# LoRaWAN_CO2_measurement_Device.net
KiCad netlist of a schematic drawn in Altium Designer
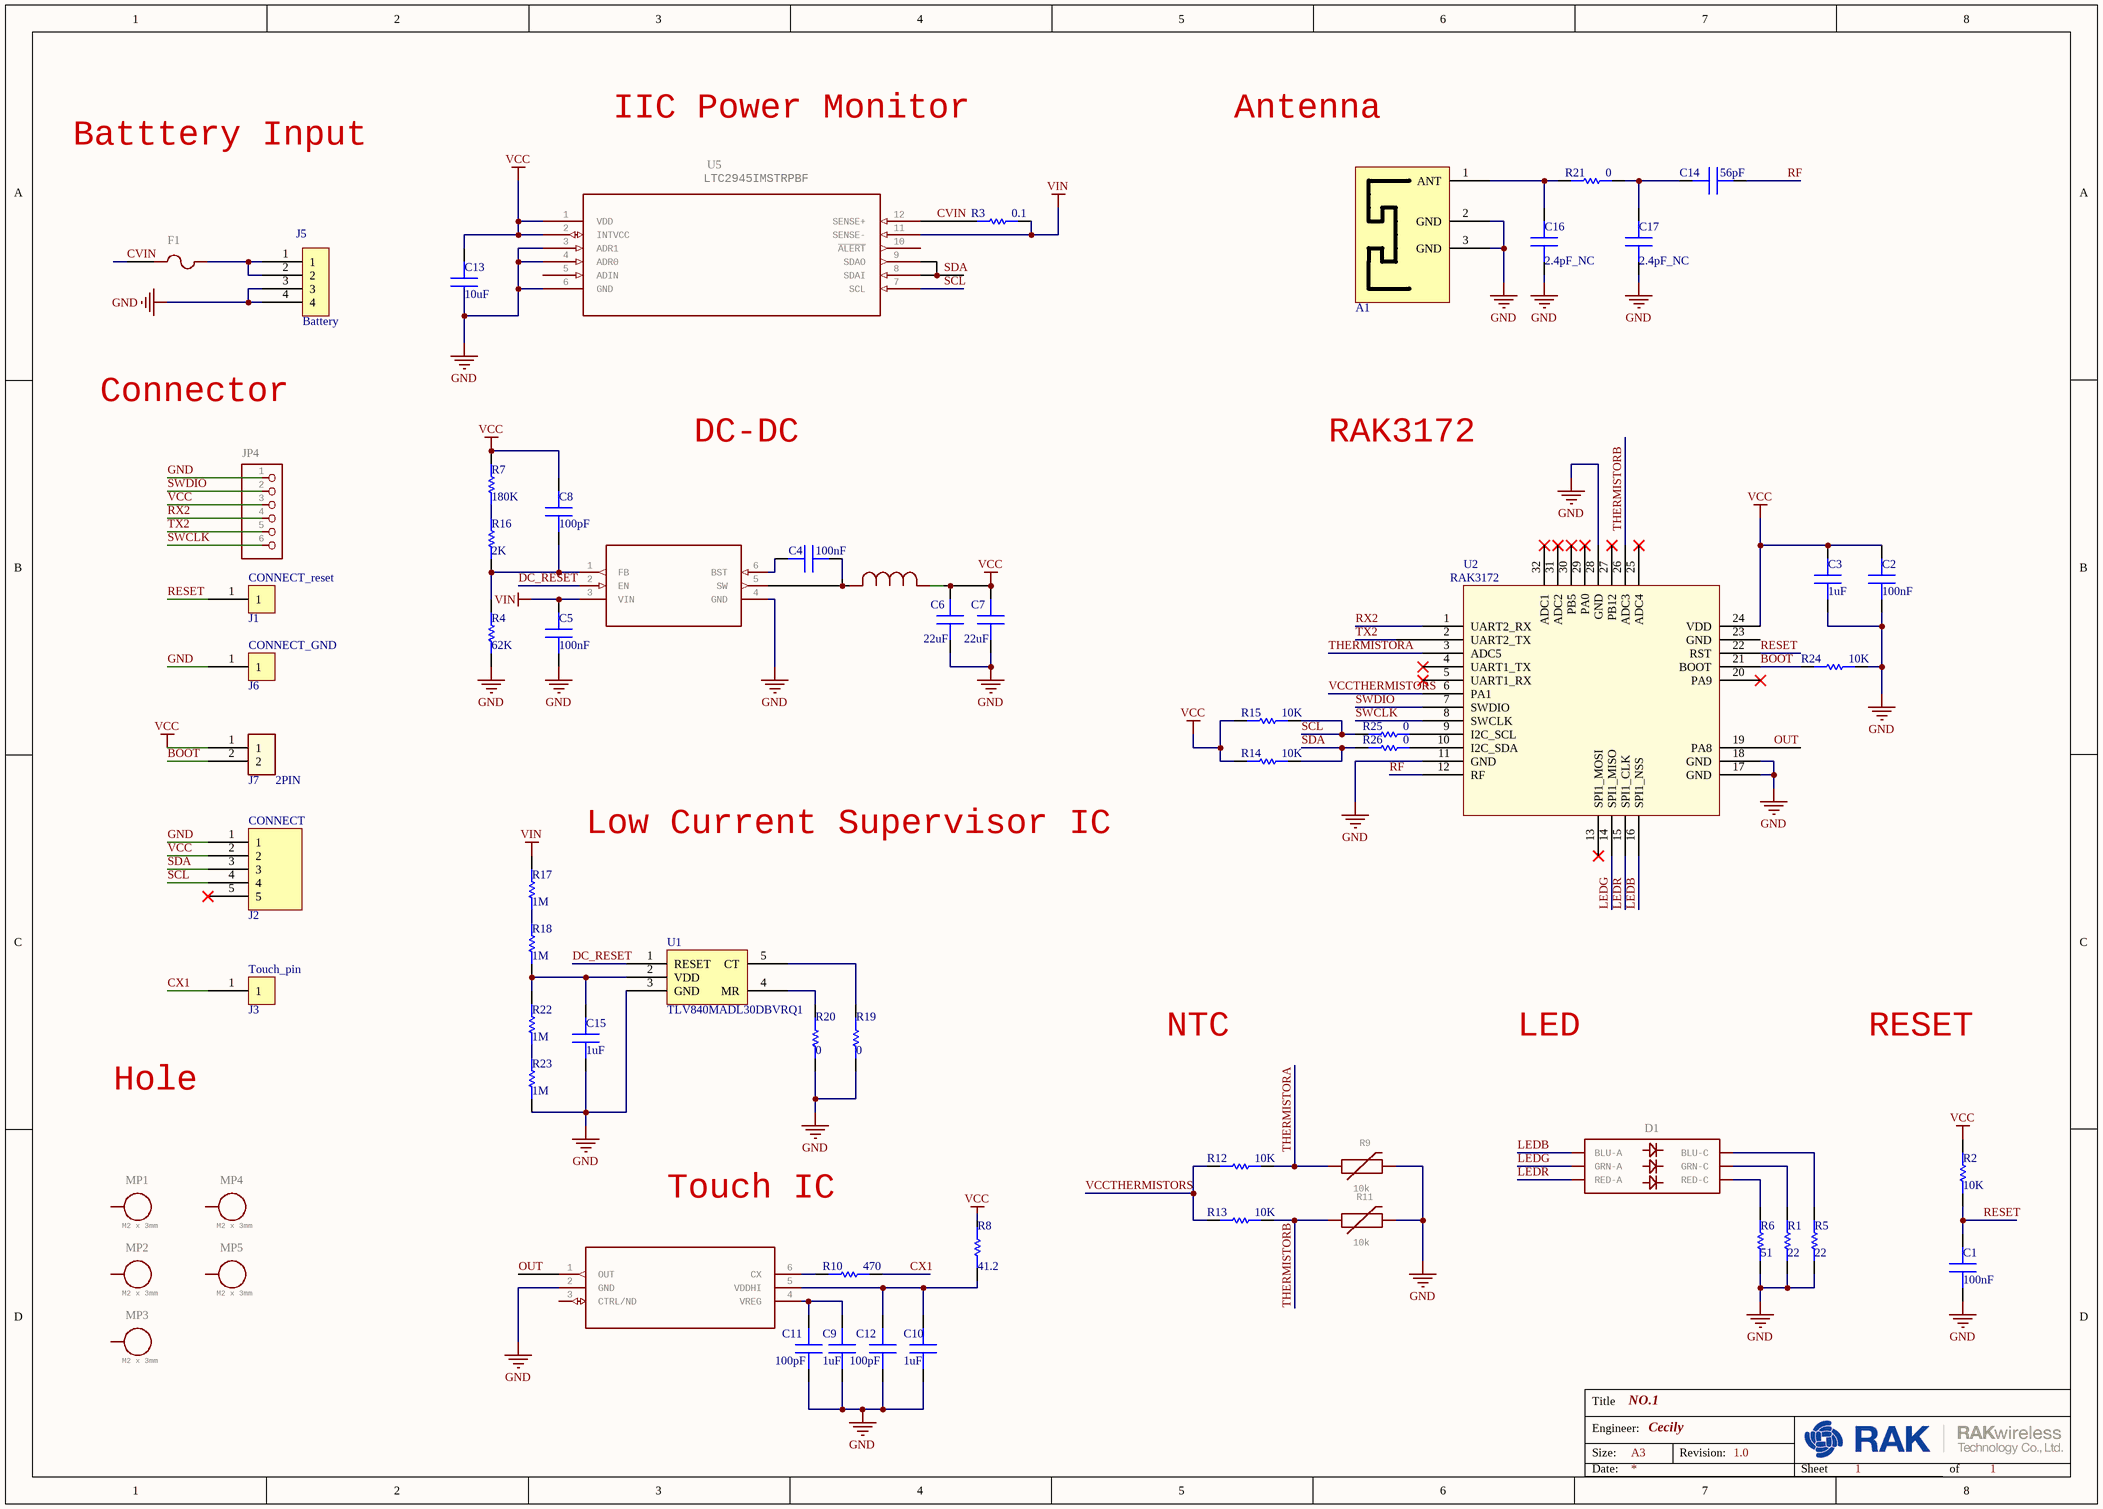
[diagram p0: LoRaWAN CO2 measurement Device.SchDoc]

(export (version "E")
  (design (tool "Eeschema 10.0.6"))
  (components
    (comp (ref "A1")
      (value "ANT_LORA_Alarm_Button")
      (footprint "ANT_LORA_Alarm_Button")
      (libsource (lib "LIBRARY_ZWW_Library") (part "ANT_LORA_Alarm_Button"))
    )
    (comp (ref "C1")
      (value "100nF")
      (footprint "sc0402")
      (description "Capacitor-10V-100nF-±10%-X5R -0402")
      (fields (field (name "MANUFACTURER") "YAGEO") (field (name "TOLERANCE") "±10%"))
      (libsource (lib "RAK_Database_Lib_2022") (part "CAPACITOR NP"))
    )
    (comp (ref "C2")
      (value "100nF")
      (footprint "sc0402")
      (description "Capacitor-10V-100nF-±10%-X5R -0402")
      (fields (field (name "MANUFACTURER") "YAGEO") (field (name "TOLERANCE") "±10%"))
      (libsource (lib "RAK_Database_Lib_2022") (part "CAPACITOR NP"))
    )
    (comp (ref "C3")
      (value "1uF")
      (footprint "sc0402")
      (description "Capacitor-10V-1uF-±10%-X5R-0402")
      (fields (field (name "MANUFACTURER") "YAGEO") (field (name "TOLERANCE") "±10%"))
      (libsource (lib "RAK_Database_Lib_2022") (part "CAPACITOR NP"))
    )
    (comp (ref "C4")
      (value "100nF")
      (footprint "sc0402")
      (description "Capacitor-10V-100nF-±10%-X5R -0402")
      (fields (field (name "MANUFACTURER") "YAGEO") (field (name "TOLERANCE") "±10%"))
      (libsource (lib "RAK_Database_Lib_2022") (part "CAPACITOR NP"))
    )
    (comp (ref "C5")
      (value "100nF")
      (footprint "sc0402")
      (description "Capacitor-10V-100nF-±10%-X5R -0402")
      (fields (field (name "MANUFACTURER") "YAGEO") (field (name "TOLERANCE") "±10%"))
      (libsource (lib "RAK_Database_Lib_2022") (part "CAPACITOR NP"))
    )
    (comp (ref "C6")
      (value "22uF")
      (footprint "sc0805")
      (description "Capacitor-25V-22uF-±20%-X5R-0805")
      (fields (field (name "MANUFACTURER") "MURATA") (field (name "TOLERANCE") "±20%"))
      (libsource (lib "RAK_Database_Lib_2022") (part "CAPACITOR NP"))
    )
    (comp (ref "C7")
      (value "22uF")
      (footprint "sc0805")
      (description "Capacitor-25V-22uF-±20%-X5R-0805")
      (fields (field (name "MANUFACTURER") "MURATA") (field (name "TOLERANCE") "±20%"))
      (libsource (lib "RAK_Database_Lib_2022") (part "CAPACITOR NP"))
    )
    (comp (ref "C8")
      (value "100pF")
      (footprint "sc0402")
      (description "Capacitor-50V-100pF-±5%-NPO-0402")
      (fields (field (name "MANUFACTURER") "YAGEO") (field (name "TOLERANCE") "±5%"))
      (libsource (lib "RAK_Database_Lib_2022") (part "CAPACITOR NP"))
    )
    (comp (ref "C9")
      (value "1uF")
      (footprint "sc0402")
      (description "Capacitor-10V-1uF-±10%-X5R-0402")
      (fields (field (name "MANUFACTURER") "YAGEO") (field (name "TOLERANCE") "±10%"))
      (libsource (lib "RAK_Database_Lib_2022") (part "CAPACITOR NP"))
    )
    (comp (ref "C10")
      (value "1uF")
      (footprint "sc0402")
      (description "Capacitor-10V-1uF-±10%-X5R-0402")
      (fields (field (name "MANUFACTURER") "YAGEO") (field (name "TOLERANCE") "±10%"))
      (libsource (lib "RAK_Database_Lib_2022") (part "CAPACITOR NP"))
    )
    (comp (ref "C11")
      (value "100pF")
      (footprint "sc0402")
      (description "Capacitor-50V-100pF-±5%-NPO-0402")
      (fields (field (name "MANUFACTURER") "YAGEO") (field (name "TOLERANCE") "±5%"))
      (libsource (lib "RAK_Database_Lib_2022") (part "CAPACITOR NP"))
    )
    (comp (ref "C12")
      (value "100pF")
      (footprint "sc0402")
      (description "Capacitor-50V-100pF-±5%-NPO-0402")
      (fields (field (name "MANUFACTURER") "YAGEO") (field (name "TOLERANCE") "±5%"))
      (libsource (lib "RAK_Database_Lib_2022") (part "CAPACITOR NP"))
    )
    (comp (ref "C13")
      (value "10uF")
      (footprint "sc0402")
      (description "Capacitor-10V-10uF-±20%-X5R-0402")
      (fields (field (name "MANUFACTURER") "YAGEO") (field (name "TOLERANCE") "±20%"))
      (libsource (lib "RAK_Database_Lib_2022") (part "CAPACITOR NP"))
    )
    (comp (ref "C14")
      (value "56pF")
      (footprint "sc0402")
      (description "Capacitor-50V-56pF-±5%-COG-0402")
      (fields (field (name "MANUFACTURER") "Murata") (field (name "TOLERANCE") "±5%"))
      (libsource (lib "RAK_Database_Lib_2022") (part "CAPACITOR NP"))
    )
    (comp (ref "C15")
      (value "1uF")
      (footprint "sc0402")
      (description "Capacitor-10V-1uF-±10%-X5R-0402")
      (fields (field (name "MANUFACTURER") "YAGEO") (field (name "TOLERANCE") "±10%"))
      (libsource (lib "RAK_Database_Lib_2022") (part "CAPACITOR NP"))
    )
    (comp (ref "C16")
      (value "2.4pF_NC")
      (footprint "sc0402")
      (description "Capacitor-50V-2.4pF-±0.1pF-COG-0402")
      (fields (field (name "MANUFACTURER") "MuRATA") (field (name "TOLERANCE") "±0.1pF"))
      (libsource (lib "RAK_Database_Lib_2022") (part "CAPACITOR NP"))
    )
    (comp (ref "C17")
      (value "2.4pF_NC")
      (footprint "sc0402")
      (description "Capacitor-50V-2.4pF-±0.1pF-COG-0402")
      (fields (field (name "MANUFACTURER") "MuRATA") (field (name "TOLERANCE") "±0.1pF"))
      (libsource (lib "RAK_Database_Lib_2022") (part "CAPACITOR NP"))
    )
    (comp (ref "CONNECT")
      (value "J2")
      (footprint "circle1*5_0.7_1.106")
      (libsource (lib "CONNECT") (part "CONNECT"))
    )
    (comp (ref "CONNECT_GND")
      (value "J6")
      (footprint "circle1*1_1.016_1.788")
      (libsource (lib "CONNECT_1") (part "CONNECT_1"))
    )
    (comp (ref "CONNECT_reset")
      (value "J1")
      (footprint "circle1*1_1.016_1.788")
      (libsource (lib "CONNECT_1") (part "CONNECT_1"))
    )
    (comp (ref "D1")
      (value "LED-RGBBRG")
      (footprint "LED-TRICOLOR-5050")
      (libsource (lib "SparkFun-LED") (part "LED-RGBBRG"))
    )
    (comp (ref "F1")
      (value "0031.7701.11")
      (footprint "FUSE_0031.7701.11_SCH")
      (fields
        (field (name "LIBRARYNAME") "fusible")
        (field (name "COPYRIGHT") "Copyright (C) 2024 Ultra Librarian. All rights reserved.")
      )
      (libsource (lib "fusible") (part "0031.7701.11"))
    )
    (comp (ref "J5") (value "Battery") (footprint "Battery_Con") (libsource (lib "Cecily") (part "Battery")))
    (comp (ref "J7")
      (value "2PIN")
      (footprint "SIP-2P")
      (description "Conn Header-Male Pin-1*2Pos-Straight-PH2.54-Through Hole-Pole3.0mm-Mating6mm-Body2.54mm")
      (fields (field (name "MANUFACTURER") "STZ01") (field (name "PART NUMBER") "ST-PH-254-0087"))
      (libsource (lib "RAK_Database_Lib_2022") (part "CONN-2"))
    )
    (comp (ref "JP4")
      (value "PINHD-1X6CB")
      (footprint "1X06-CLEANBIG")
      (description "PIN HEADER")
      (fields (field (name "LIBRARYNAME") "holes_no_keep"))
      (libsource (lib "holes_no_keep") (part "PINHD-1X6CB"))
    )
    (comp (ref "L1")
      (value "SD14-6R9-R")
      (footprint "IND_CB_SD14")
      (fields
        (field (name "LIBRARYNAME") "inductor_eaton_6.9uh")
        (field (name "COPYRIGHT") "Copyright (C) 2024 Ultra Librarian. All rights reserved.")
      )
      (libsource (lib "inductor_eaton_6.9uh") (part "SD14-6R9-R"))
    )
    (comp (ref "MP1")
      (value "M2 x 3mm")
      (footprint "WA-SMSI_9774030243")
      (libsource (lib "Eagle_WA-SMSI_rev21a") (part "WA-SMSI_9774XXX243_9774030243R"))
    )
    (comp (ref "MP2")
      (value "M2 x 3mm")
      (footprint "WA-SMSI_9774030243")
      (libsource (lib "Eagle_WA-SMSI_rev21a") (part "WA-SMSI_9774XXX243_9774030243R"))
    )
    (comp (ref "MP3")
      (value "M2 x 3mm")
      (footprint "WA-SMSI_9774030243")
      (libsource (lib "Eagle_WA-SMSI_rev21a") (part "WA-SMSI_9774XXX243_9774030243R"))
    )
    (comp (ref "MP4")
      (value "M2 x 3mm")
      (footprint "WA-SMSI_9774030243")
      (libsource (lib "Eagle_WA-SMSI_rev21a") (part "WA-SMSI_9774XXX243_9774030243R"))
    )
    (comp (ref "MP5")
      (value "M2 x 3mm")
      (footprint "WA-SMSI_9774030243")
      (libsource (lib "Eagle_WA-SMSI_rev21a") (part "WA-SMSI_9774XXX243_9774030243R"))
    )
    (comp (ref "R1")
      (value "22")
      (footprint "sr0402")
      (description "Resistor-1/16W-22Ω-±5%-0402")
      (fields (field (name "MANUFACTURER") "YAGEO") (field (name "PART NUMBER") "RC0402JR-0722RL"))
      (libsource (lib "RAK_Database_Lib_2022") (part "RESISTOR"))
    )
    (comp (ref "R2")
      (value "10K")
      (footprint "sr0402")
      (description "Resistor-1/16W-10KΩ-±1％-0402")
      (fields (field (name "MANUFACTURER") "YAGEO") (field (name "PART NUMBER") "RC0402FR-0710KL"))
      (libsource (lib "RAK_Database_Lib_2022") (part "RESISTOR"))
    )
    (comp (ref "R3")
      (value "0.1")
      (footprint "sr1210")
      (description "Resistor-1/2W-100mΩ-±1％-1210")
      (fields (field (name "MANUFACTURER") "PANSONIC") (field (name "PART NUMBER") "ERJ-14BSFR10U"))
      (libsource (lib "RAK_Database_Lib_2022") (part "RESISTOR"))
    )
    (comp (ref "R4")
      (value "62K")
      (footprint "sr0402")
      (description "Resistor-1/16W-62KΩ-±1%-0402")
      (fields (field (name "MANUFACTURER") "YAGEO") (field (name "PART NUMBER") "RC0402FR-0762KL"))
      (libsource (lib "RAK_Database_Lib_2022") (part "RESISTOR"))
    )
    (comp (ref "R5")
      (value "22")
      (footprint "sr0402")
      (description "Resistor-1/16W-22Ω-±5%-0402")
      (fields (field (name "MANUFACTURER") "YAGEO") (field (name "PART NUMBER") "RC0402JR-0722RL"))
      (libsource (lib "RAK_Database_Lib_2022") (part "RESISTOR"))
    )
    (comp (ref "R6")
      (value "51")
      (footprint "sr0402")
      (description "Resistor-1/16W-51Ω-±5%-0402")
      (fields (field (name "MANUFACTURER") "YAGEO") (field (name "PART NUMBER") "RC0402JR-0751RL"))
      (libsource (lib "RAK_Database_Lib_2022") (part "RESISTOR"))
    )
    (comp (ref "R7")
      (value "180K")
      (footprint "sr0402")
      (description "Resistor-1/16W-180KΩ-±1%-0402")
      (fields (field (name "MANUFACTURER") "YAGEO") (field (name "PART NUMBER") "RC0402FR-07180KL"))
      (libsource (lib "RAK_Database_Lib_2022") (part "RESISTOR"))
    )
    (comp (ref "R8")
      (value "41.2")
      (footprint "sr0402")
      (description "Resistor-1/16W-41.2Ω-±1%-0402")
      (fields (field (name "MANUFACTURER") "YAGEO") (field (name "PART NUMBER") "RC0402FR-0741R2L"))
      (libsource (lib "RAK_Database_Lib_2022") (part "RESISTOR"))
    )
    (comp (ref "R9")
      (value "10k")
      (footprint "AXIAL-0.1")
      (libsource (lib "SparkFun-Resistors") (part "NTC-THERMISTOR-AXIAL-0.1"))
    )
    (comp (ref "R10")
      (value "470")
      (footprint "sr0402")
      (description "Resistor-1/16W-470Ω-±1%-0402")
      (fields (field (name "MANUFACTURER") "YAGEO") (field (name "PART NUMBER") "RC0402FR-07470RL"))
      (libsource (lib "RAK_Database_Lib_2022") (part "RESISTOR"))
    )
    (comp (ref "R11")
      (value "10k")
      (footprint "AXIAL-0.1")
      (libsource (lib "SparkFun-Resistors") (part "NTC-THERMISTOR-AXIAL-0.1"))
    )
    (comp (ref "R12")
      (value "10K")
      (footprint "sr0402")
      (description "Resistor-1/16W-10KΩ-±1％-0402")
      (fields (field (name "MANUFACTURER") "YAGEO") (field (name "PART NUMBER") "RC0402FR-0710KL"))
      (libsource (lib "RAK_Database_Lib_2022") (part "RESISTOR"))
    )
    (comp (ref "R13")
      (value "10K")
      (footprint "sr0402")
      (description "Resistor-1/16W-10KΩ-±1％-0402")
      (fields (field (name "MANUFACTURER") "YAGEO") (field (name "PART NUMBER") "RC0402FR-0710KL"))
      (libsource (lib "RAK_Database_Lib_2022") (part "RESISTOR"))
    )
    (comp (ref "R14")
      (value "10K")
      (footprint "sr0402")
      (description "Resistor-1/16W-10KΩ-±1％-0402")
      (fields (field (name "MANUFACTURER") "YAGEO") (field (name "PART NUMBER") "RC0402FR-0710KL"))
      (libsource (lib "RAK_Database_Lib_2022") (part "RESISTOR"))
    )
    (comp (ref "R15")
      (value "10K")
      (footprint "sr0402")
      (description "Resistor-1/16W-10KΩ-±1％-0402")
      (fields (field (name "MANUFACTURER") "YAGEO") (field (name "PART NUMBER") "RC0402FR-0710KL"))
      (libsource (lib "RAK_Database_Lib_2022") (part "RESISTOR"))
    )
    (comp (ref "R16")
      (value "2K")
      (footprint "sr0402")
      (description "Resistor-1/16W-2KΩ-±1%-0402")
      (fields (field (name "MANUFACTURER") "YAGEO") (field (name "PART NUMBER") "RC0402FR-072KL"))
      (libsource (lib "RAK_Database_Lib_2022") (part "RESISTOR"))
    )
    (comp (ref "R17")
      (value "1M")
      (footprint "sr0402")
      (description "Resistor-1/16W-1MΩ-±1％-0402")
      (fields (field (name "MANUFACTURER") "YAGEO") (field (name "PART NUMBER") "RC0402FR-071ML"))
      (libsource (lib "RAK_Database_Lib_2022") (part "RESISTOR"))
    )
    (comp (ref "R18")
      (value "1M")
      (footprint "sr0402")
      (description "Resistor-1/16W-1MΩ-±1％-0402")
      (fields (field (name "MANUFACTURER") "YAGEO") (field (name "PART NUMBER") "RC0402FR-071ML"))
      (libsource (lib "RAK_Database_Lib_2022") (part "RESISTOR"))
    )
    (comp (ref "R19")
      (value "0")
      (footprint "sr0402")
      (description "Resistor-0Ω-1A-50mΩMAX-0402")
      (fields (field (name "MANUFACTURER") "YAGEO") (field (name "PART NUMBER") "RC0402JR-070RL"))
      (libsource (lib "RAK_Database_Lib_2022") (part "RESISTOR"))
    )
    (comp (ref "R20")
      (value "0")
      (footprint "sr0402")
      (description "Resistor-0Ω-1A-50mΩMAX-0402")
      (fields (field (name "MANUFACTURER") "YAGEO") (field (name "PART NUMBER") "RC0402JR-070RL"))
      (libsource (lib "RAK_Database_Lib_2022") (part "RESISTOR"))
    )
    (comp (ref "R21")
      (value "0")
      (footprint "sr0402")
      (description "Resistor-0Ω-1A-50mΩMAX-0402")
      (fields (field (name "MANUFACTURER") "YAGEO") (field (name "PART NUMBER") "RC0402JR-070RL"))
      (libsource (lib "RAK_Database_Lib_2022") (part "RESISTOR"))
    )
    (comp (ref "R22")
      (value "1M")
      (footprint "sr0402")
      (description "Resistor-1/16W-1MΩ-±1％-0402")
      (fields (field (name "MANUFACTURER") "YAGEO") (field (name "PART NUMBER") "RC0402FR-071ML"))
      (libsource (lib "RAK_Database_Lib_2022") (part "RESISTOR"))
    )
    (comp (ref "R23")
      (value "1M")
      (footprint "sr0402")
      (description "Resistor-1/16W-1MΩ-±1％-0402")
      (fields (field (name "MANUFACTURER") "YAGEO") (field (name "PART NUMBER") "RC0402FR-071ML"))
      (libsource (lib "RAK_Database_Lib_2022") (part "RESISTOR"))
    )
    (comp (ref "R24")
      (value "10K")
      (footprint "sr0402")
      (description "Resistor-1/16W-10KΩ-±1％-0402")
      (fields (field (name "MANUFACTURER") "YAGEO") (field (name "PART NUMBER") "RC0402FR-0710KL"))
      (libsource (lib "RAK_Database_Lib_2022") (part "RESISTOR"))
    )
    (comp (ref "R25")
      (value "0")
      (footprint "sr0402")
      (description "Resistor-0Ω-1A-50mΩMAX-0402")
      (fields (field (name "MANUFACTURER") "YAGEO") (field (name "PART NUMBER") "RC0402JR-070RL"))
      (libsource (lib "RAK_Database_Lib_2022") (part "RESISTOR"))
    )
    (comp (ref "R26")
      (value "0")
      (footprint "sr0402")
      (description "Resistor-0Ω-1A-50mΩMAX-0402")
      (fields (field (name "MANUFACTURER") "YAGEO") (field (name "PART NUMBER") "RC0402JR-070RL"))
      (libsource (lib "RAK_Database_Lib_2022") (part "RESISTOR"))
    )
    (comp (ref "Touch_pin")
      (value "J3")
      (footprint "circle1*1_0.7")
      (libsource (lib "CONNECT_1") (part "CONNECT_1"))
    )
    (comp (ref "U1")
      (value "TLV840MADL30DBVRQ1")
      (footprint "TLV840_SOT-23-5_L2.9-W1.6-P0.95-LS2.8-BR")
      (libsource (lib "TLV840") (part "TLV840"))
    )
    (comp (ref "U2")
      (value "RAK3172")
      (footprint "RAK3172")
      (libsource (lib "RAK_Symbol_Library") (part "RAK3172"))
    )
    (comp (ref "U3")
      (value "AP63200WU-7")
      (footprint "TSOT26_DIO")
      (fields (field (name "COPYRIGHT") "Copyright (C) 2024 Ultra Librarian. All rights reserved."))
      (libsource (lib "AP63200") (part "AP63200WU-7"))
    )
    (comp (ref "U4")
      (value "IQS228B00000000TSR")
      (footprint "TSOT23-6_AZQ")
      (fields
        (field (name "LIBRARYNAME") "Azeto")
        (field (name "COPYRIGHT") "Copyright (C) 2024 Ultra Librarian. All rights reserved.")
      )
      (libsource (lib "Azeto") (part "IQS228B00000000TSR"))
    )
    (comp (ref "U5")
      (value "LTC2945IMSTRPBF")
      (footprint "MSOP-12_MS_LIT")
      (fields
        (field (name "MANUFACTURER_PART_NUMBER") "LTC2945IMS#TRPBF")
        (field (name "COPYRIGHT") "Copyright (C) 2025 Ultra Librarian. All rights reserved.")
      )
      (libsource (lib "ltc2945") (part "LTC2945IMSTRPBF"))
    )
  )
  (nets
    (net (code "1") (name "/BOOT") (class "Default")
      (node (ref "J7") (pin "2") (pinfunction "2_2") (pintype "passive"))
      (node (ref "R24") (pin "1") (pinfunction "1_1") (pintype "passive"))
      (node (ref "U2") (pin "21") (pinfunction "BOOT_21") (pintype "passive"))
    )
    (net (code "2") (name "/CVIN") (class "Default")
      (node (ref "F1") (pin "2") (pinfunction "2_2") (pintype "passive"))
      (node (ref "R3") (pin "2") (pinfunction "2_2") (pintype "passive"))
      (node (ref "U5") (pin "12") (pinfunction "SENSE+_12") (pintype "input"))
    )
    (net (code "3") (name "/CX1") (class "Default")
      (node (ref "R10") (pin "1") (pinfunction "1_1") (pintype "passive"))
      (node (ref "Touch_pin") (pin "1") (pinfunction "1_1") (pintype "passive"))
    )
    (net (code "4") (name "/DC_RESET") (class "Default")
      (node (ref "U1") (pin "1") (pinfunction "RESET_1") (pintype "passive"))
      (node (ref "U3") (pin "2") (pinfunction "EN_2") (pintype "input"))
    )
    (net (code "5") (name "/LEDB") (class "Default")
      (node (ref "D1") (pin "6") (pinfunction "BLU-A_6") (pintype "bidirectional"))
      (node (ref "U2") (pin "16") (pinfunction "SPI1_NSS_16") (pintype "passive"))
    )
    (net (code "6") (name "/LEDG") (class "Default")
      (node (ref "D1") (pin "4") (pinfunction "GRN-A_4") (pintype "bidirectional"))
      (node (ref "U2") (pin "14") (pinfunction "SPI1_MISO_14") (pintype "passive"))
    )
    (net (code "7") (name "/LEDR") (class "Default")
      (node (ref "D1") (pin "5") (pinfunction "RED-A_5") (pintype "bidirectional"))
      (node (ref "U2") (pin "15") (pinfunction "SPI1_CLK_15") (pintype "passive"))
    )
    (net (code "8") (name "/OUT") (class "Default")
      (node (ref "U2") (pin "19") (pinfunction "PA8_19") (pintype "passive"))
      (node (ref "U4") (pin "1") (pinfunction "OUT_1") (pintype "output"))
    )
    (net (code "9") (name "/RESET") (class "Default")
      (node (ref "C1") (pin "1") (pinfunction "POS_1") (pintype "passive"))
      (node (ref "CONNECT_reset") (pin "1") (pinfunction "1_1") (pintype "passive"))
      (node (ref "R2") (pin "2") (pinfunction "2_2") (pintype "passive"))
      (node (ref "U2") (pin "22") (pinfunction "RST_22") (pintype "passive"))
    )
    (net (code "10") (name "/RF") (class "Default")
      (node (ref "C14") (pin "2") (pinfunction "NEG_2") (pintype "passive"))
      (node (ref "U2") (pin "12") (pinfunction "RF_12") (pintype "passive"))
    )
    (net (code "11") (name "/RX2") (class "Default")
      (node (ref "JP4") (pin "4") (pinfunction "4_4") (pintype "passive"))
      (node (ref "U2") (pin "1") (pinfunction "UART2_RX_1") (pintype "passive"))
    )
    (net (code "12") (name "/SCL") (class "Default")
      (node (ref "CONNECT") (pin "4") (pinfunction "4_4") (pintype "passive"))
      (node (ref "R15") (pin "1") (pinfunction "1_1") (pintype "passive"))
      (node (ref "R25") (pin "2") (pinfunction "2_2") (pintype "passive"))
      (node (ref "U5") (pin "7") (pinfunction "SCL_7") (pintype "input"))
    )
    (net (code "13") (name "/SDA") (class "Default")
      (node (ref "CONNECT") (pin "3") (pinfunction "3_3") (pintype "passive"))
      (node (ref "R14") (pin "1") (pinfunction "1_1") (pintype "passive"))
      (node (ref "R26") (pin "2") (pinfunction "2_2") (pintype "passive"))
      (node (ref "U5") (pin "8") (pinfunction "SDAI_8") (pintype "input"))
      (node (ref "U5") (pin "9") (pinfunction "SDAO_9") (pintype "output"))
    )
    (net (code "14") (name "/SWCLK") (class "Default")
      (node (ref "JP4") (pin "6") (pinfunction "6_6") (pintype "passive"))
      (node (ref "U2") (pin "8") (pinfunction "SWCLK_8") (pintype "passive"))
    )
    (net (code "15") (name "/SWDIO") (class "Default")
      (node (ref "JP4") (pin "2") (pinfunction "2_2") (pintype "passive"))
      (node (ref "U2") (pin "7") (pinfunction "SWDIO_7") (pintype "passive"))
    )
    (net (code "16") (name "/THERMISTORA") (class "Default")
      (node (ref "R12") (pin "2") (pinfunction "2_2") (pintype "passive"))
      (node (ref "R9") (pin "P$1") (pinfunction "1_P$1") (pintype "bidirectional"))
      (node (ref "U2") (pin "3") (pinfunction "ADC5_3") (pintype "passive"))
    )
    (net (code "17") (name "/THERMISTORB") (class "Default")
      (node (ref "R11") (pin "P$1") (pinfunction "1_P$1") (pintype "bidirectional"))
      (node (ref "R13") (pin "2") (pinfunction "2_2") (pintype "passive"))
      (node (ref "U2") (pin "26") (pinfunction "ADC3_26") (pintype "passive"))
    )
    (net (code "18") (name "/TX2") (class "Default")
      (node (ref "JP4") (pin "5") (pinfunction "5_5") (pintype "passive"))
      (node (ref "U2") (pin "2") (pinfunction "UART2_TX_2") (pintype "passive"))
    )
    (net (code "19") (name "/VCCTHERMISTORS") (class "Default")
      (node (ref "R12") (pin "1") (pinfunction "1_1") (pintype "passive"))
      (node (ref "R13") (pin "1") (pinfunction "1_1") (pintype "passive"))
      (node (ref "U2") (pin "6") (pinfunction "PA1_6") (pintype "passive"))
    )
    (net (code "20") (name "GND") (class "Default")
      (node (ref "A1") (pin "2") (pinfunction "GND_2") (pintype "passive"))
      (node (ref "A1") (pin "3") (pinfunction "GND_3") (pintype "passive"))
      (node (ref "C1") (pin "2") (pinfunction "NEG_2") (pintype "passive"))
      (node (ref "C10") (pin "1") (pinfunction "POS_1") (pintype "passive"))
      (node (ref "C11") (pin "1") (pinfunction "POS_1") (pintype "passive"))
      (node (ref "C12") (pin "1") (pinfunction "POS_1") (pintype "passive"))
      (node (ref "C13") (pin "1") (pinfunction "POS_1") (pintype "passive"))
      (node (ref "C15") (pin "1") (pinfunction "POS_1") (pintype "passive"))
      (node (ref "C16") (pin "1") (pinfunction "POS_1") (pintype "passive"))
      (node (ref "C17") (pin "1") (pinfunction "POS_1") (pintype "passive"))
      (node (ref "C2") (pin "2") (pinfunction "NEG_2") (pintype "passive"))
      (node (ref "C3") (pin "1") (pinfunction "POS_1") (pintype "passive"))
      (node (ref "C5") (pin "2") (pinfunction "NEG_2") (pintype "passive"))
      (node (ref "C6") (pin "1") (pinfunction "POS_1") (pintype "passive"))
      (node (ref "C7") (pin "1") (pinfunction "POS_1") (pintype "passive"))
      (node (ref "C9") (pin "1") (pinfunction "POS_1") (pintype "passive"))
      (node (ref "CONNECT") (pin "1") (pinfunction "1_1") (pintype "passive"))
      (node (ref "CONNECT_GND") (pin "1") (pinfunction "1_1") (pintype "passive"))
      (node (ref "J5") (pin "3") (pinfunction "3_3") (pintype "passive"))
      (node (ref "J5") (pin "4") (pinfunction "4_4") (pintype "passive"))
      (node (ref "JP4") (pin "1") (pinfunction "1_1") (pintype "passive"))
      (node (ref "R1") (pin "1") (pinfunction "1_1") (pintype "passive"))
      (node (ref "R11") (pin "P$2") (pinfunction "2_P$2") (pintype "bidirectional"))
      (node (ref "R19") (pin "1") (pinfunction "1_1") (pintype "passive"))
      (node (ref "R20") (pin "1") (pinfunction "1_1") (pintype "passive"))
      (node (ref "R23") (pin "1") (pinfunction "1_1") (pintype "passive"))
      (node (ref "R24") (pin "2") (pinfunction "2_2") (pintype "passive"))
      (node (ref "R4") (pin "1") (pinfunction "1_1") (pintype "passive"))
      (node (ref "R5") (pin "1") (pinfunction "1_1") (pintype "passive"))
      (node (ref "R6") (pin "1") (pinfunction "1_1") (pintype "passive"))
      (node (ref "R9") (pin "P$2") (pinfunction "2_P$2") (pintype "bidirectional"))
      (node (ref "U1") (pin "3") (pinfunction "GND_3") (pintype "passive"))
      (node (ref "U2") (pin "11") (pinfunction "GND_11") (pintype "passive"))
      (node (ref "U2") (pin "17") (pinfunction "GND_17") (pintype "passive"))
      (node (ref "U2") (pin "18") (pinfunction "GND_18") (pintype "passive"))
      (node (ref "U2") (pin "28") (pinfunction "GND_28") (pintype "passive"))
      (node (ref "U3") (pin "4") (pinfunction "GND_4") (pintype "passive"))
      (node (ref "U4") (pin "2") (pinfunction "GND_2") (pintype "passive"))
      (node (ref "U5") (pin "3") (pinfunction "ADR1_3") (pintype "input"))
      (node (ref "U5") (pin "4") (pinfunction "ADR0_4") (pintype "input"))
      (node (ref "U5") (pin "6") (pinfunction "GND_6") (pintype "power_in"))
    )
    (net (code "21") (name "Net-(A1-ANT)") (class "Default")
      (node (ref "A1") (pin "1") (pinfunction "ANT_1") (pintype "passive"))
      (node (ref "C16") (pin "2") (pinfunction "NEG_2") (pintype "passive"))
      (node (ref "R21") (pin "2") (pinfunction "2_2") (pintype "passive"))
    )
    (net (code "22") (name "Net-(C4-NEG)") (class "Default")
      (node (ref "C4") (pin "2") (pinfunction "NEG_2") (pintype "passive"))
      (node (ref "L1") (pin "2") (pinfunction "2_2") (pintype "passive"))
      (node (ref "U3") (pin "5") (pinfunction "SW_5") (pintype "output"))
    )
    (net (code "23") (name "Net-(C4-POS)") (class "Default")
      (node (ref "C4") (pin "1") (pinfunction "POS_1") (pintype "passive"))
      (node (ref "U3") (pin "6") (pinfunction "BST_6") (pintype "input"))
    )
    (net (code "24") (name "Net-(C8-POS)") (class "Default")
      (node (ref "C8") (pin "1") (pinfunction "POS_1") (pintype "passive"))
      (node (ref "R16") (pin "1") (pinfunction "1_1") (pintype "passive"))
      (node (ref "R4") (pin "2") (pinfunction "2_2") (pintype "passive"))
      (node (ref "U3") (pin "1") (pinfunction "FB_1") (pintype "output"))
    )
    (net (code "25") (name "Net-(C10-NEG)") (class "Default")
      (node (ref "C10") (pin "2") (pinfunction "NEG_2") (pintype "passive"))
      (node (ref "C12") (pin "2") (pinfunction "NEG_2") (pintype "passive"))
      (node (ref "R8") (pin "1") (pinfunction "1_1") (pintype "passive"))
      (node (ref "U4") (pin "5") (pinfunction "VDDHI_5") (pintype "power_in"))
    )
    (net (code "26") (name "Net-(C11-NEG)") (class "Default")
      (node (ref "C11") (pin "2") (pinfunction "NEG_2") (pintype "passive"))
      (node (ref "C9") (pin "2") (pinfunction "NEG_2") (pintype "passive"))
      (node (ref "U4") (pin "4") (pinfunction "VREG_4") (pintype "passive"))
    )
    (net (code "27") (name "Net-(C14-POS)") (class "Default")
      (node (ref "C14") (pin "1") (pinfunction "POS_1") (pintype "passive"))
      (node (ref "C17") (pin "2") (pinfunction "NEG_2") (pintype "passive"))
      (node (ref "R21") (pin "1") (pinfunction "1_1") (pintype "passive"))
    )
    (net (code "28") (name "Net-(C15-NEG)") (class "Default")
      (node (ref "C15") (pin "2") (pinfunction "NEG_2") (pintype "passive"))
      (node (ref "R18") (pin "1") (pinfunction "1_1") (pintype "passive"))
      (node (ref "R22") (pin "2") (pinfunction "2_2") (pintype "passive"))
      (node (ref "U1") (pin "2") (pinfunction "VDD_2") (pintype "passive"))
    )
    (net (code "29") (name "Net-(D1-BLU-C)") (class "Default")
      (node (ref "D1") (pin "1") (pinfunction "BLU-C_1") (pintype "bidirectional"))
      (node (ref "R5") (pin "2") (pinfunction "2_2") (pintype "passive"))
    )
    (net (code "30") (name "Net-(D1-GRN-C)") (class "Default")
      (node (ref "D1") (pin "3") (pinfunction "GRN-C_3") (pintype "bidirectional"))
      (node (ref "R1") (pin "2") (pinfunction "2_2") (pintype "passive"))
    )
    (net (code "31") (name "Net-(D1-RED-C)") (class "Default")
      (node (ref "D1") (pin "2") (pinfunction "RED-C_2") (pintype "bidirectional"))
      (node (ref "R6") (pin "2") (pinfunction "2_2") (pintype "passive"))
    )
    (net (code "32") (name "Net-(F1-Pad1)") (class "Default")
      (node (ref "F1") (pin "1") (pinfunction "1_1") (pintype "passive"))
      (node (ref "J5") (pin "1") (pinfunction "1_1") (pintype "passive"))
      (node (ref "J5") (pin "2") (pinfunction "2_2") (pintype "passive"))
    )
    (net (code "33") (name "Net-(R16-Pad2)") (class "Default")
      (node (ref "R16") (pin "2") (pinfunction "2_2") (pintype "passive"))
      (node (ref "R7") (pin "2") (pinfunction "2_2") (pintype "passive"))
    )
    (net (code "34") (name "Net-(R17-Pad1)") (class "Default")
      (node (ref "R17") (pin "1") (pinfunction "1_1") (pintype "passive"))
      (node (ref "R18") (pin "2") (pinfunction "2_2") (pintype "passive"))
    )
    (net (code "35") (name "Net-(R22-Pad1)") (class "Default")
      (node (ref "R22") (pin "1") (pinfunction "1_1") (pintype "passive"))
      (node (ref "R23") (pin "2") (pinfunction "2_2") (pintype "passive"))
    )
    (net (code "36") (name "Net-(U1-CT)") (class "Default")
      (node (ref "R19") (pin "2") (pinfunction "2_2") (pintype "passive"))
      (node (ref "U1") (pin "5") (pinfunction "CT_5") (pintype "passive"))
    )
    (net (code "37") (name "Net-(U1-MR)") (class "Default")
      (node (ref "R20") (pin "2") (pinfunction "2_2") (pintype "passive"))
      (node (ref "U1") (pin "4") (pinfunction "MR_4") (pintype "passive"))
    )
    (net (code "38") (name "Net-(U2-I2C_SCL)") (class "Default")
      (node (ref "R25") (pin "1") (pinfunction "1_1") (pintype "passive"))
      (node (ref "U2") (pin "9") (pinfunction "I2C_SCL_9") (pintype "passive"))
    )
    (net (code "39") (name "Net-(U2-I2C_SDA)") (class "Default")
      (node (ref "R26") (pin "1") (pinfunction "1_1") (pintype "passive"))
      (node (ref "U2") (pin "10") (pinfunction "I2C_SDA_10") (pintype "passive"))
    )
    (net (code "40") (name "Net-(U4-CX)") (class "Default")
      (node (ref "R10") (pin "2") (pinfunction "2_2") (pintype "passive"))
      (node (ref "U4") (pin "6") (pinfunction "CX_6") (pintype "passive"))
    )
    (net (code "41") (name "VCC") (class "Default")
      (node (ref "C13") (pin "2") (pinfunction "NEG_2") (pintype "passive"))
      (node (ref "C2") (pin "1") (pinfunction "POS_1") (pintype "passive"))
      (node (ref "C3") (pin "2") (pinfunction "NEG_2") (pintype "passive"))
      (node (ref "C6") (pin "2") (pinfunction "NEG_2") (pintype "passive"))
      (node (ref "C7") (pin "2") (pinfunction "NEG_2") (pintype "passive"))
      (node (ref "C8") (pin "2") (pinfunction "NEG_2") (pintype "passive"))
      (node (ref "CONNECT") (pin "2") (pinfunction "2_2") (pintype "passive"))
      (node (ref "J7") (pin "1") (pinfunction "1_1") (pintype "passive"))
      (node (ref "JP4") (pin "3") (pinfunction "3_3") (pintype "passive"))
      (node (ref "L1") (pin "1") (pinfunction "1_1") (pintype "passive"))
      (node (ref "R14") (pin "2") (pinfunction "2_2") (pintype "passive"))
      (node (ref "R15") (pin "2") (pinfunction "2_2") (pintype "passive"))
      (node (ref "R2") (pin "1") (pinfunction "1_1") (pintype "passive"))
      (node (ref "R7") (pin "1") (pinfunction "1_1") (pintype "passive"))
      (node (ref "R8") (pin "2") (pinfunction "2_2") (pintype "passive"))
      (node (ref "U2") (pin "24") (pinfunction "VDD_24") (pintype "passive"))
      (node (ref "U5") (pin "1") (pinfunction "VDD_1") (pintype "power_in"))
      (node (ref "U5") (pin "2") (pinfunction "INTVCC_2") (pintype "bidirectional"))
    )
    (net (code "42") (name "VIN") (class "Default")
      (node (ref "C5") (pin "1") (pinfunction "POS_1") (pintype "passive"))
      (node (ref "R17") (pin "2") (pinfunction "2_2") (pintype "passive"))
      (node (ref "R3") (pin "1") (pinfunction "1_1") (pintype "passive"))
      (node (ref "U3") (pin "3") (pinfunction "VIN_3") (pintype "power_in"))
      (node (ref "U5") (pin "11") (pinfunction "SENSE-_11") (pintype "input"))
    )
    (net (code "43") (name "unconnected-(CONNECT-Pad5)") (class "Default")
      (node (ref "CONNECT") (pin "5") (pinfunction "5_5") (pintype "passive+no_connect"))
    )
    (net (code "44") (name "unconnected-(MP1-Pad1)") (class "Default")
      (node (ref "MP1") (pin "1") (pinfunction "1_1") (pintype "passive"))
    )
    (net (code "45") (name "unconnected-(MP2-Pad1)") (class "Default")
      (node (ref "MP2") (pin "1") (pinfunction "1_1") (pintype "passive"))
    )
    (net (code "46") (name "unconnected-(MP3-Pad1)") (class "Default")
      (node (ref "MP3") (pin "1") (pinfunction "1_1") (pintype "passive"))
    )
    (net (code "47") (name "unconnected-(MP4-Pad1)") (class "Default")
      (node (ref "MP4") (pin "1") (pinfunction "1_1") (pintype "passive"))
    )
    (net (code "48") (name "unconnected-(MP5-Pad1)") (class "Default")
      (node (ref "MP5") (pin "1") (pinfunction "1_1") (pintype "passive"))
    )
    (net (code "49") (name "unconnected-(U2-ADC1-Pad32)") (class "Default")
      (node (ref "U2") (pin "32") (pinfunction "ADC1_32") (pintype "passive+no_connect"))
    )
    (net (code "50") (name "unconnected-(U2-ADC2-Pad31)") (class "Default")
      (node (ref "U2") (pin "31") (pinfunction "ADC2_31") (pintype "passive+no_connect"))
    )
    (net (code "51") (name "unconnected-(U2-ADC4-Pad25)") (class "Default")
      (node (ref "U2") (pin "25") (pinfunction "ADC4_25") (pintype "passive+no_connect"))
    )
    (net (code "52") (name "unconnected-(U2-GND-Pad23)") (class "Default")
      (node (ref "U2") (pin "23") (pinfunction "GND_23") (pintype "passive"))
    )
    (net (code "53") (name "unconnected-(U2-PA0-Pad29)") (class "Default")
      (node (ref "U2") (pin "29") (pinfunction "PA0_29") (pintype "passive+no_connect"))
    )
    (net (code "54") (name "unconnected-(U2-PA9-Pad20)") (class "Default")
      (node (ref "U2") (pin "20") (pinfunction "PA9_20") (pintype "passive+no_connect"))
    )
    (net (code "55") (name "unconnected-(U2-PB5-Pad30)") (class "Default")
      (node (ref "U2") (pin "30") (pinfunction "PB5_30") (pintype "passive+no_connect"))
    )
    (net (code "56") (name "unconnected-(U2-PB12-Pad27)") (class "Default")
      (node (ref "U2") (pin "27") (pinfunction "PB12_27") (pintype "passive+no_connect"))
    )
    (net (code "57") (name "unconnected-(U2-SPI1_MOSI-Pad13)") (class "Default")
      (node (ref "U2") (pin "13") (pinfunction "SPI1_MOSI_13") (pintype "passive+no_connect"))
    )
    (net (code "58") (name "unconnected-(U2-UART1_RX-Pad5)") (class "Default")
      (node (ref "U2") (pin "5") (pinfunction "UART1_RX_5") (pintype "passive+no_connect"))
    )
    (net (code "59") (name "unconnected-(U2-UART1_TX-Pad4)") (class "Default")
      (node (ref "U2") (pin "4") (pinfunction "UART1_TX_4") (pintype "passive+no_connect"))
    )
    (net (code "60") (name "unconnected-(U4-CTRL{slash}ND-Pad3)") (class "Default")
      (node (ref "U4") (pin "3") (pinfunction "CTRL/ND_3") (pintype "bidirectional"))
    )
    (net (code "61") (name "unconnected-(U5-ADIN-Pad5)") (class "Default")
      (node (ref "U5") (pin "5") (pinfunction "ADIN_5") (pintype "input"))
    )
    (net (code "62") (name "unconnected-(U5-~{ALERT}-Pad10)") (class "Default")
      (node (ref "U5") (pin "10") (pinfunction "~{ALERT}_10") (pintype "output"))
    )
  )
)
